# Camera_Cage_Breakout.net
KiCad netlist of a schematic drawn in EAGLE
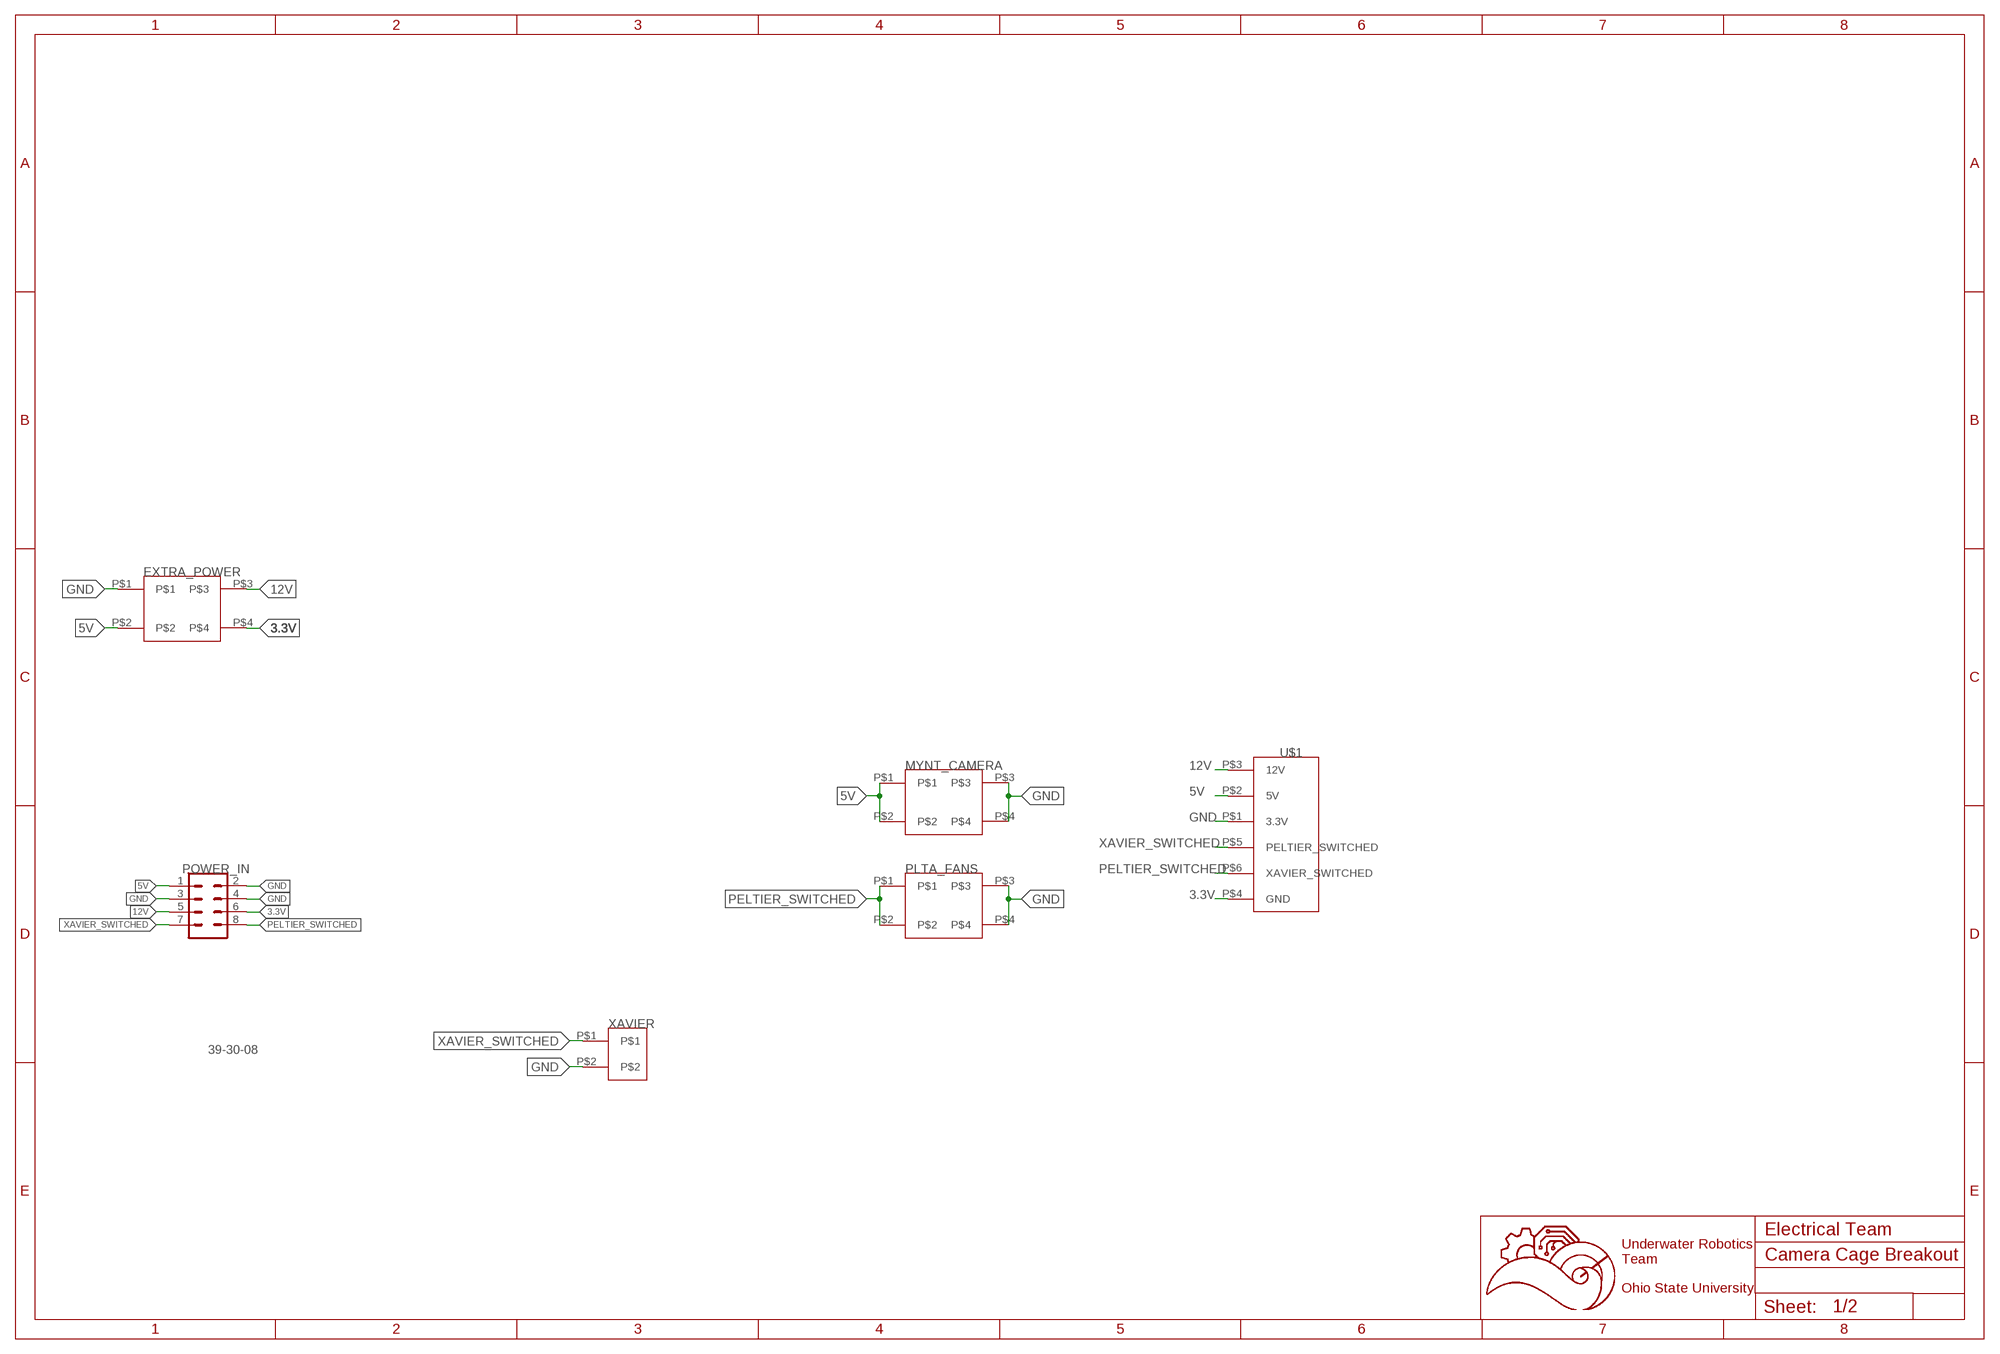
[diagram p0: schematic, sheet 1]
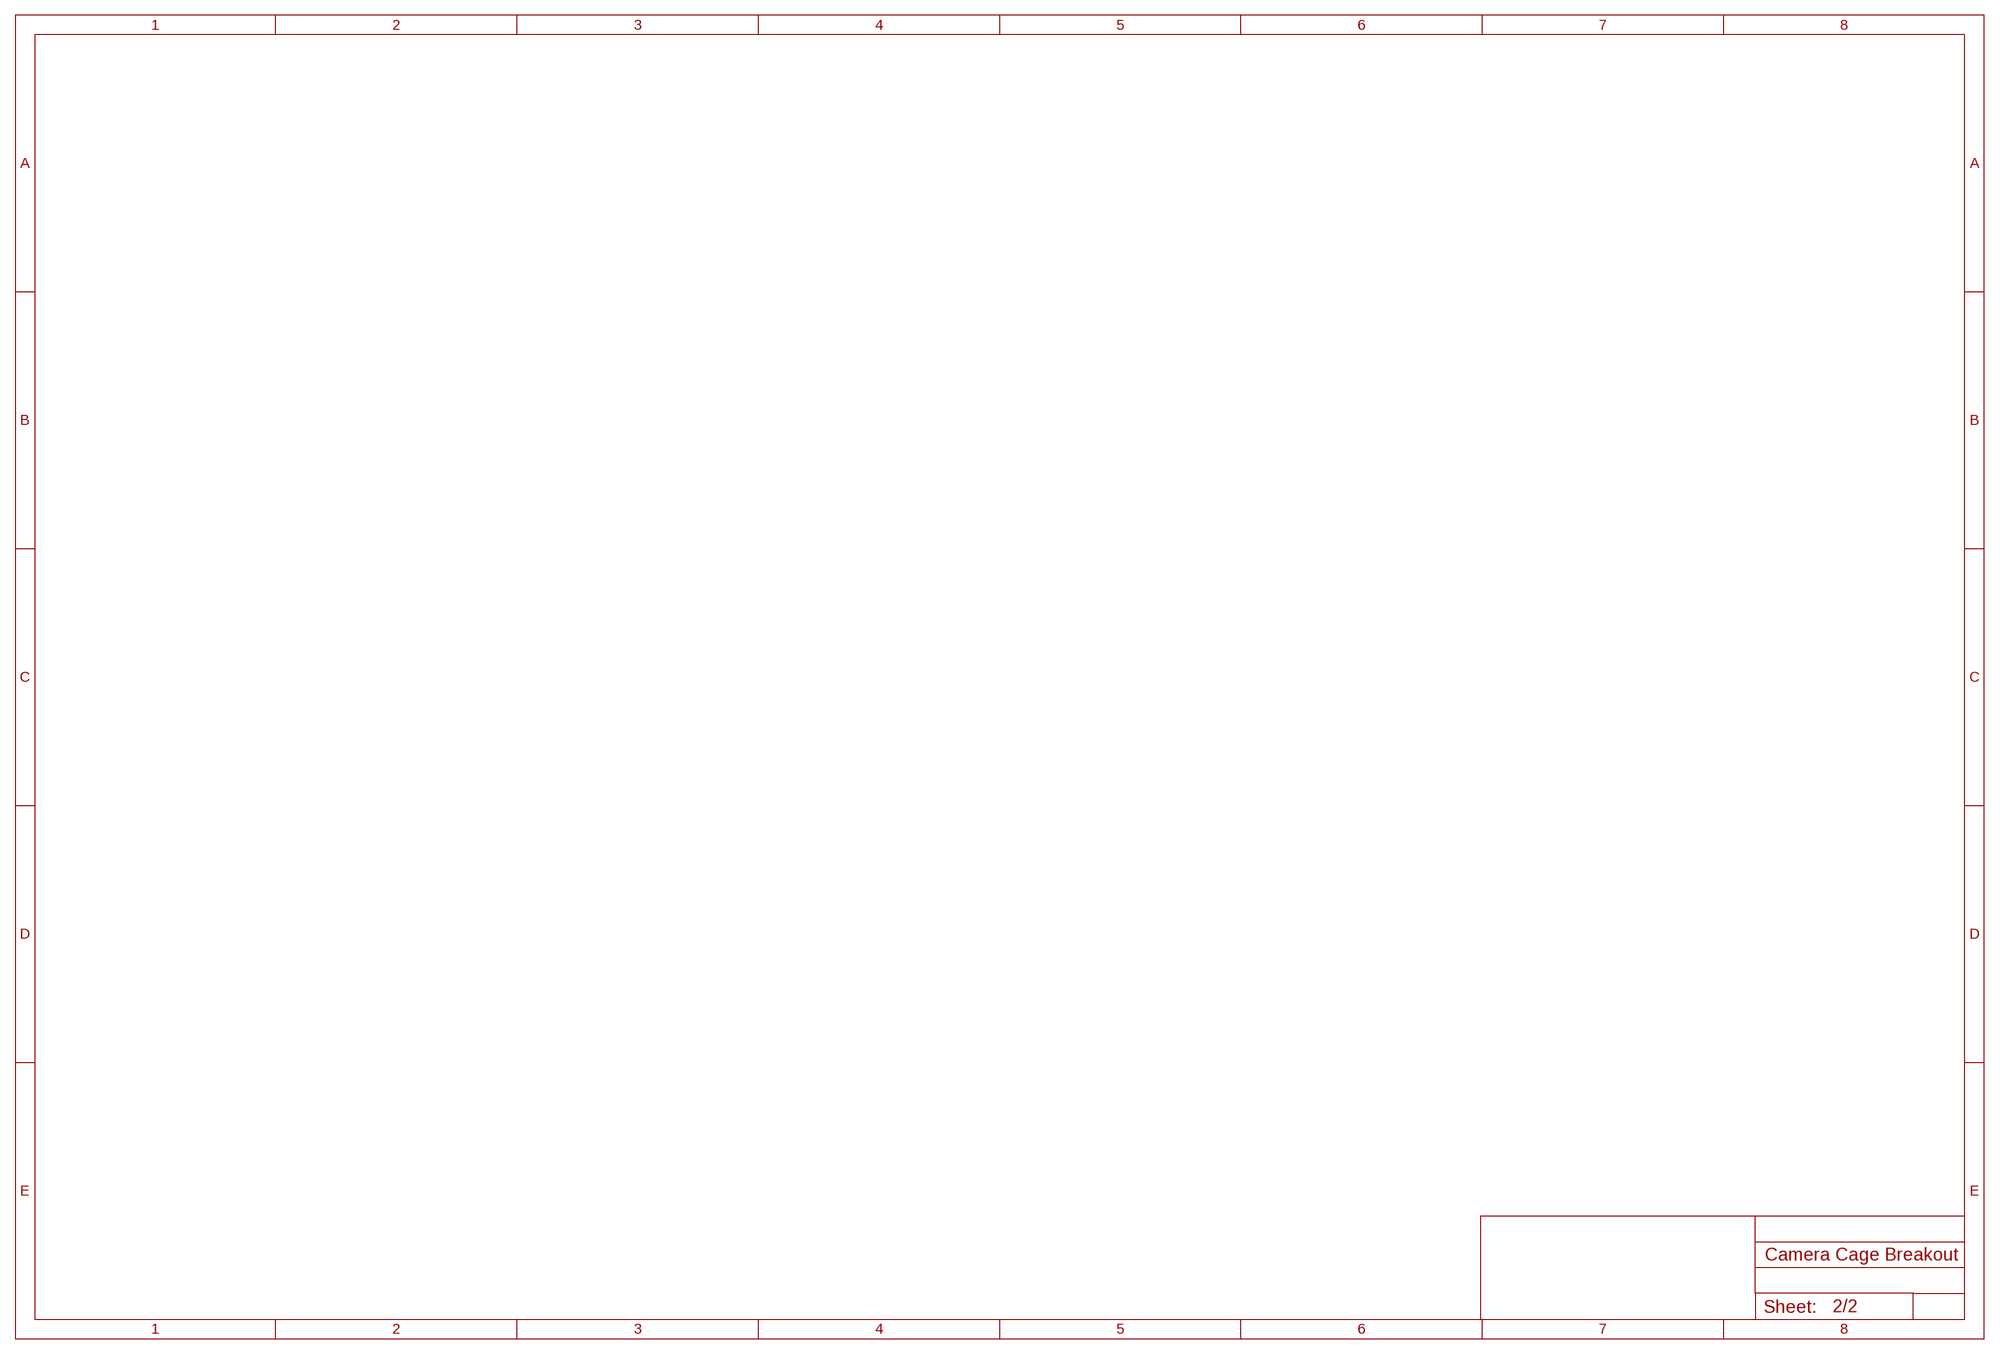
[diagram p1: schematic, sheet 2]

(export (version "E")
  (design (tool "Eeschema 10.0.6"))
  (components
    (comp (ref "EXTRA_POWER")
      (value "4PIN-VERT")
      (footprint "eagle-import:4PIN-VERT")
      (libsource (lib "eagle-import") (part "4PIN-VERT"))
    )
    (comp (ref "MYNT_CAMERA")
      (value "4PIN-VERT")
      (footprint "eagle-import:4PIN-VERT")
      (libsource (lib "eagle-import") (part "4PIN-VERT"))
    )
    (comp (ref "PLTA_FANS")
      (value "4PIN-VERT")
      (footprint "eagle-import:4PIN-VERT")
      (libsource (lib "eagle-import") (part "4PIN-VERT"))
    )
    (comp (ref "POWER_IN")
      (value "39-30-08")
      (footprint "eagle-import:39-30-_08_")
      (libsource (lib "eagle-import") (part "39-30-?08?"))
    )
    (comp (ref "U$1")
      (value "CAMERA_CAGE_TEST")
      (footprint "eagle-import:6-PIN")
      (libsource (lib "eagle-import") (part "CAMERA_CAGE_TEST"))
    )
    (comp (ref "XAVIER")
      (value "2PIN-VERT")
      (footprint "eagle-import:2PIN-VERT")
      (libsource (lib "eagle-import") (part "2PIN-VERT"))
    )
  )
  (nets
    (net (code "1") (name "3.3V") (class "Default")
      (node (ref "EXTRA_POWER") (pin "P$4") (pinfunction "P$4_P$4") (pintype "bidirectional"))
      (node (ref "POWER_IN") (pin "6") (pinfunction "6_6") (pintype "passive"))
      (node (ref "U$1") (pin "P$4") (pinfunction "GND_P$4") (pintype "bidirectional"))
    )
    (net (code "2") (name "5V") (class "Default")
      (node (ref "EXTRA_POWER") (pin "P$2") (pinfunction "P$2_P$2") (pintype "bidirectional"))
      (node (ref "MYNT_CAMERA") (pin "P$1") (pinfunction "P$1_P$1") (pintype "bidirectional"))
      (node (ref "MYNT_CAMERA") (pin "P$2") (pinfunction "P$2_P$2") (pintype "bidirectional"))
      (node (ref "POWER_IN") (pin "1") (pinfunction "1_1") (pintype "passive"))
      (node (ref "U$1") (pin "P$2") (pinfunction "5V_P$2") (pintype "bidirectional"))
    )
    (net (code "3") (name "12V") (class "Default")
      (node (ref "EXTRA_POWER") (pin "P$3") (pinfunction "P$3_P$3") (pintype "bidirectional"))
      (node (ref "POWER_IN") (pin "5") (pinfunction "5_5") (pintype "passive"))
      (node (ref "U$1") (pin "P$3") (pinfunction "12V_P$3") (pintype "bidirectional"))
    )
    (net (code "4") (name "GND") (class "Default")
      (node (ref "EXTRA_POWER") (pin "P$1") (pinfunction "P$1_P$1") (pintype "bidirectional"))
      (node (ref "MYNT_CAMERA") (pin "P$3") (pinfunction "P$3_P$3") (pintype "bidirectional"))
      (node (ref "MYNT_CAMERA") (pin "P$4") (pinfunction "P$4_P$4") (pintype "bidirectional"))
      (node (ref "PLTA_FANS") (pin "P$3") (pinfunction "P$3_P$3") (pintype "bidirectional"))
      (node (ref "PLTA_FANS") (pin "P$4") (pinfunction "P$4_P$4") (pintype "bidirectional"))
      (node (ref "POWER_IN") (pin "2") (pinfunction "2_2") (pintype "passive"))
      (node (ref "POWER_IN") (pin "3") (pinfunction "3_3") (pintype "passive"))
      (node (ref "POWER_IN") (pin "4") (pinfunction "4_4") (pintype "passive"))
      (node (ref "U$1") (pin "P$1") (pinfunction "3.3V_P$1") (pintype "bidirectional"))
      (node (ref "XAVIER") (pin "P$2") (pinfunction "P$2_P$2") (pintype "bidirectional"))
    )
    (net (code "5") (name "PELTIER_SWITCHED") (class "Default")
      (node (ref "PLTA_FANS") (pin "P$1") (pinfunction "P$1_P$1") (pintype "bidirectional"))
      (node (ref "PLTA_FANS") (pin "P$2") (pinfunction "P$2_P$2") (pintype "bidirectional"))
      (node (ref "POWER_IN") (pin "8") (pinfunction "8_8") (pintype "passive"))
      (node (ref "U$1") (pin "P$6") (pinfunction "XAVIER_SWITCHED_P$6") (pintype "bidirectional"))
    )
    (net (code "6") (name "XAVIER_SWITCHED") (class "Default")
      (node (ref "POWER_IN") (pin "7") (pinfunction "7_7") (pintype "passive"))
      (node (ref "U$1") (pin "P$5") (pinfunction "PELTIER_SWITCHED_P$5") (pintype "bidirectional"))
      (node (ref "XAVIER") (pin "P$1") (pinfunction "P$1_P$1") (pintype "bidirectional"))
    )
  )
)
